# main.net
KiCad netlist of a schematic drawn in EAGLE
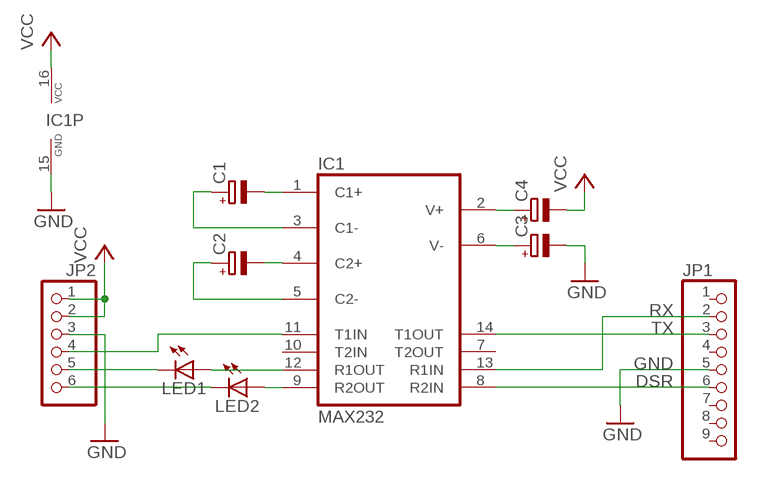
[diagram p0: schematic, sheet 1]

(export (version "E")
  (design (tool "Eeschema 10.0.6"))
  (components
    (comp (ref "C1")
      (value "CPOL-EUB45181A")
      (footprint "eagle-import:B45181A")
      (libsource (lib "eagle-import") (part "CPOL-EUB45181A"))
    )
    (comp (ref "C2")
      (value "CPOL-EUB45181A")
      (footprint "eagle-import:B45181A")
      (libsource (lib "eagle-import") (part "CPOL-EUB45181A"))
    )
    (comp (ref "C3")
      (value "CPOL-EUB45181A")
      (footprint "eagle-import:B45181A")
      (libsource (lib "eagle-import") (part "CPOL-EUB45181A"))
    )
    (comp (ref "C4")
      (value "CPOL-EUB45181A")
      (footprint "eagle-import:B45181A")
      (libsource (lib "eagle-import") (part "CPOL-EUB45181A"))
    )
    (comp (ref "IC1")
      (value "MAX232")
      (footprint "eagle-import:DIL16")
      (fields (field (name "MF") "MAXIM") (field (name "MPN") "MAX232ACPE+"))
      (libsource (lib "eagle-import") (part "MAX232"))
    )
    (comp (ref "JP1")
      (value "PINHD-1X9")
      (footprint "eagle-import:1X09")
      (libsource (lib "eagle-import") (part "PINHD-1X9"))
    )
    (comp (ref "JP2")
      (value "PINHD-1X6")
      (footprint "eagle-import:1X06")
      (libsource (lib "eagle-import") (part "PINHD-1X6"))
    )
    (comp (ref "LED1")
      (value "LED3MM")
      (footprint "eagle-import:LED3MM")
      (libsource (lib "eagle-import") (part "LED3MM"))
    )
    (comp (ref "LED2")
      (value "LED3MM")
      (footprint "eagle-import:LED3MM")
      (libsource (lib "eagle-import") (part "LED3MM"))
    )
  )
  (nets
    (net (code "1") (name "/DSR") (class "Default")
      (node (ref "IC1") (pin "8") (pinfunction "R2IN_8") (pintype "input"))
      (node (ref "JP1") (pin "6") (pinfunction "6_6") (pintype "passive"))
    )
    (net (code "2") (name "/RX") (class "Default")
      (node (ref "IC1") (pin "13") (pinfunction "R1IN_13") (pintype "input"))
      (node (ref "JP1") (pin "2") (pinfunction "2_2") (pintype "passive"))
    )
    (net (code "3") (name "/TX") (class "Default")
      (node (ref "IC1") (pin "14") (pinfunction "T1OUT_14") (pintype "output"))
      (node (ref "JP1") (pin "3") (pinfunction "3_3") (pintype "passive"))
    )
    (net (code "4") (name "GND") (class "Default")
      (node (ref "C3") (pin "-") (pinfunction "-_-") (pintype "passive"))
      (node (ref "IC1") (pin "15") (pinfunction "GND_15") (pintype "power_in"))
      (node (ref "JP1") (pin "5") (pinfunction "5_5") (pintype "passive"))
      (node (ref "JP2") (pin "3") (pinfunction "3_3") (pintype "passive"))
    )
    (net (code "5") (name "Net-(IC1A-C1+)") (class "Default")
      (node (ref "C1") (pin "-") (pinfunction "-_-") (pintype "passive"))
      (node (ref "IC1") (pin "1") (pinfunction "C1+_1") (pintype "bidirectional"))
    )
    (net (code "6") (name "Net-(IC1A-C1-)") (class "Default")
      (node (ref "C1") (pin "+") (pinfunction "+_+") (pintype "passive"))
      (node (ref "IC1") (pin "3") (pinfunction "C1-_3") (pintype "bidirectional"))
    )
    (net (code "7") (name "Net-(IC1A-C2+)") (class "Default")
      (node (ref "C2") (pin "-") (pinfunction "-_-") (pintype "passive"))
      (node (ref "IC1") (pin "4") (pinfunction "C2+_4") (pintype "bidirectional"))
    )
    (net (code "8") (name "Net-(IC1A-C2-)") (class "Default")
      (node (ref "C2") (pin "+") (pinfunction "+_+") (pintype "passive"))
      (node (ref "IC1") (pin "5") (pinfunction "C2-_5") (pintype "bidirectional"))
    )
    (net (code "9") (name "Net-(IC1A-R1OUT)") (class "Default")
      (node (ref "IC1") (pin "12") (pinfunction "R1OUT_12") (pintype "output"))
      (node (ref "LED1") (pin "A") (pinfunction "A_A") (pintype "passive"))
    )
    (net (code "10") (name "Net-(IC1A-R2OUT)") (class "Default")
      (node (ref "IC1") (pin "9") (pinfunction "R2OUT_9") (pintype "output"))
      (node (ref "LED2") (pin "A") (pinfunction "A_A") (pintype "passive"))
    )
    (net (code "11") (name "Net-(IC1A-T1IN)") (class "Default")
      (node (ref "IC1") (pin "11") (pinfunction "T1IN_11") (pintype "input"))
      (node (ref "JP2") (pin "4") (pinfunction "4_4") (pintype "passive"))
    )
    (net (code "12") (name "Net-(IC1A-V+)") (class "Default")
      (node (ref "C4") (pin "+") (pinfunction "+_+") (pintype "passive"))
      (node (ref "IC1") (pin "2") (pinfunction "V+_2") (pintype "bidirectional"))
    )
    (net (code "13") (name "Net-(IC1A-V-)") (class "Default")
      (node (ref "C3") (pin "+") (pinfunction "+_+") (pintype "passive"))
      (node (ref "IC1") (pin "6") (pinfunction "V-_6") (pintype "bidirectional"))
    )
    (net (code "14") (name "Net-(LED1-C)") (class "Default")
      (node (ref "JP2") (pin "5") (pinfunction "5_5") (pintype "passive"))
      (node (ref "LED1") (pin "K") (pinfunction "C_K") (pintype "passive"))
    )
    (net (code "15") (name "Net-(LED2-C)") (class "Default")
      (node (ref "JP2") (pin "6") (pinfunction "6_6") (pintype "passive"))
      (node (ref "LED2") (pin "K") (pinfunction "C_K") (pintype "passive"))
    )
    (net (code "16") (name "VCC") (class "Default")
      (node (ref "C4") (pin "-") (pinfunction "-_-") (pintype "passive"))
      (node (ref "IC1") (pin "16") (pinfunction "VCC_16") (pintype "power_in"))
      (node (ref "JP2") (pin "1") (pinfunction "1_1") (pintype "passive"))
      (node (ref "JP2") (pin "2") (pinfunction "2_2") (pintype "passive"))
    )
    (net (code "17") (name "unconnected-(IC1A-T2IN-Pad10)") (class "Default")
      (node (ref "IC1") (pin "10") (pinfunction "T2IN_10") (pintype "input"))
    )
    (net (code "18") (name "unconnected-(IC1A-T2OUT-Pad7)") (class "Default")
      (node (ref "IC1") (pin "7") (pinfunction "T2OUT_7") (pintype "output"))
    )
    (net (code "19") (name "unconnected-(JP1-Pad1)") (class "Default")
      (node (ref "JP1") (pin "1") (pinfunction "1_1") (pintype "passive"))
    )
    (net (code "20") (name "unconnected-(JP1-Pad4)") (class "Default")
      (node (ref "JP1") (pin "4") (pinfunction "4_4") (pintype "passive"))
    )
    (net (code "21") (name "unconnected-(JP1-Pad7)") (class "Default")
      (node (ref "JP1") (pin "7") (pinfunction "7_7") (pintype "passive"))
    )
    (net (code "22") (name "unconnected-(JP1-Pad8)") (class "Default")
      (node (ref "JP1") (pin "8") (pinfunction "8_8") (pintype "passive"))
    )
    (net (code "23") (name "unconnected-(JP1-Pad9)") (class "Default")
      (node (ref "JP1") (pin "9") (pinfunction "9_9") (pintype "passive"))
    )
  )
)
